# TPS3702_Breakout.net
KiCad netlist of a schematic drawn in Altium Designer
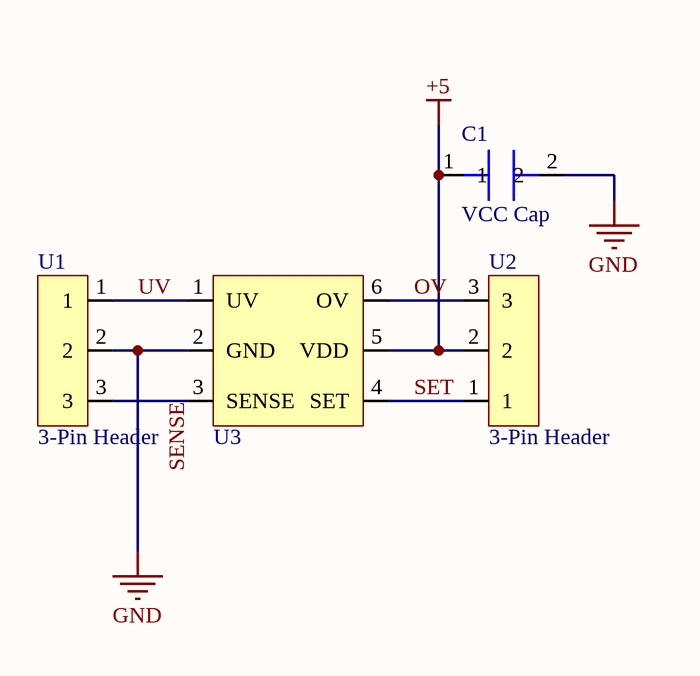
[diagram p0: TPS3702_Breakout.SchDoc]

(export (version "E")
  (design (tool "Eeschema 10.0.6"))
  (components
    (comp (ref "C1")
      (value "VCC Cap")
      (footprint "VCC Cap")
      (description "Noise Reducing Cap")
      (libsource (lib "TPS3702_Breakout") (part "VCC Cap"))
    )
    (comp (ref "U1")
      (value "3-Pin Header")
      (footprint "3-Pin Header")
      (description "standard 0.1 inch socket for headers")
      (libsource (lib "") (part "3-Pin Header_1"))
    )
    (comp (ref "U2")
      (value "3-Pin Header")
      (footprint "3-Pin Header")
      (description "standard 0.1 inch socket for headers")
      (libsource (lib "TPS3702_Breakout") (part "3-Pin Header"))
    )
    (comp (ref "U3")
      (value "TPS3702")
      (footprint "TPS3702")
      (description "voltage watchdog ic")
      (libsource (lib "TPS3702_Breakout") (part "TPS3702"))
    )
  )
  (nets
    (net (code "1") (name "+5") (class "Default")
      (node (ref "C1") (pin "1") (pinfunction "1_1") (pintype "passive"))
      (node (ref "U2") (pin "2") (pinfunction "2_2") (pintype "passive"))
      (node (ref "U3") (pin "5") (pinfunction "VDD_5") (pintype "passive"))
    )
    (net (code "2") (name "/OV") (class "Default")
      (node (ref "U2") (pin "3") (pinfunction "3_3") (pintype "passive"))
      (node (ref "U3") (pin "6") (pinfunction "OV_6") (pintype "passive"))
    )
    (net (code "3") (name "/SENSE") (class "Default")
      (node (ref "U1") (pin "3") (pinfunction "3_3") (pintype "passive"))
      (node (ref "U3") (pin "3") (pinfunction "SENSE_3") (pintype "passive"))
    )
    (net (code "4") (name "/SET") (class "Default")
      (node (ref "U2") (pin "1") (pinfunction "1_1") (pintype "passive"))
      (node (ref "U3") (pin "4") (pinfunction "SET_4") (pintype "passive"))
    )
    (net (code "5") (name "/UV") (class "Default")
      (node (ref "U1") (pin "1") (pinfunction "1_1") (pintype "passive"))
      (node (ref "U3") (pin "1") (pinfunction "UV_1") (pintype "passive"))
    )
    (net (code "6") (name "GND") (class "Default")
      (node (ref "C1") (pin "2") (pinfunction "2_2") (pintype "passive"))
      (node (ref "U1") (pin "2") (pinfunction "2_2") (pintype "passive"))
      (node (ref "U3") (pin "2") (pinfunction "GND_2") (pintype "passive"))
    )
  )
)
